# panocama.net
KiCad netlist of a schematic drawn in EAGLE
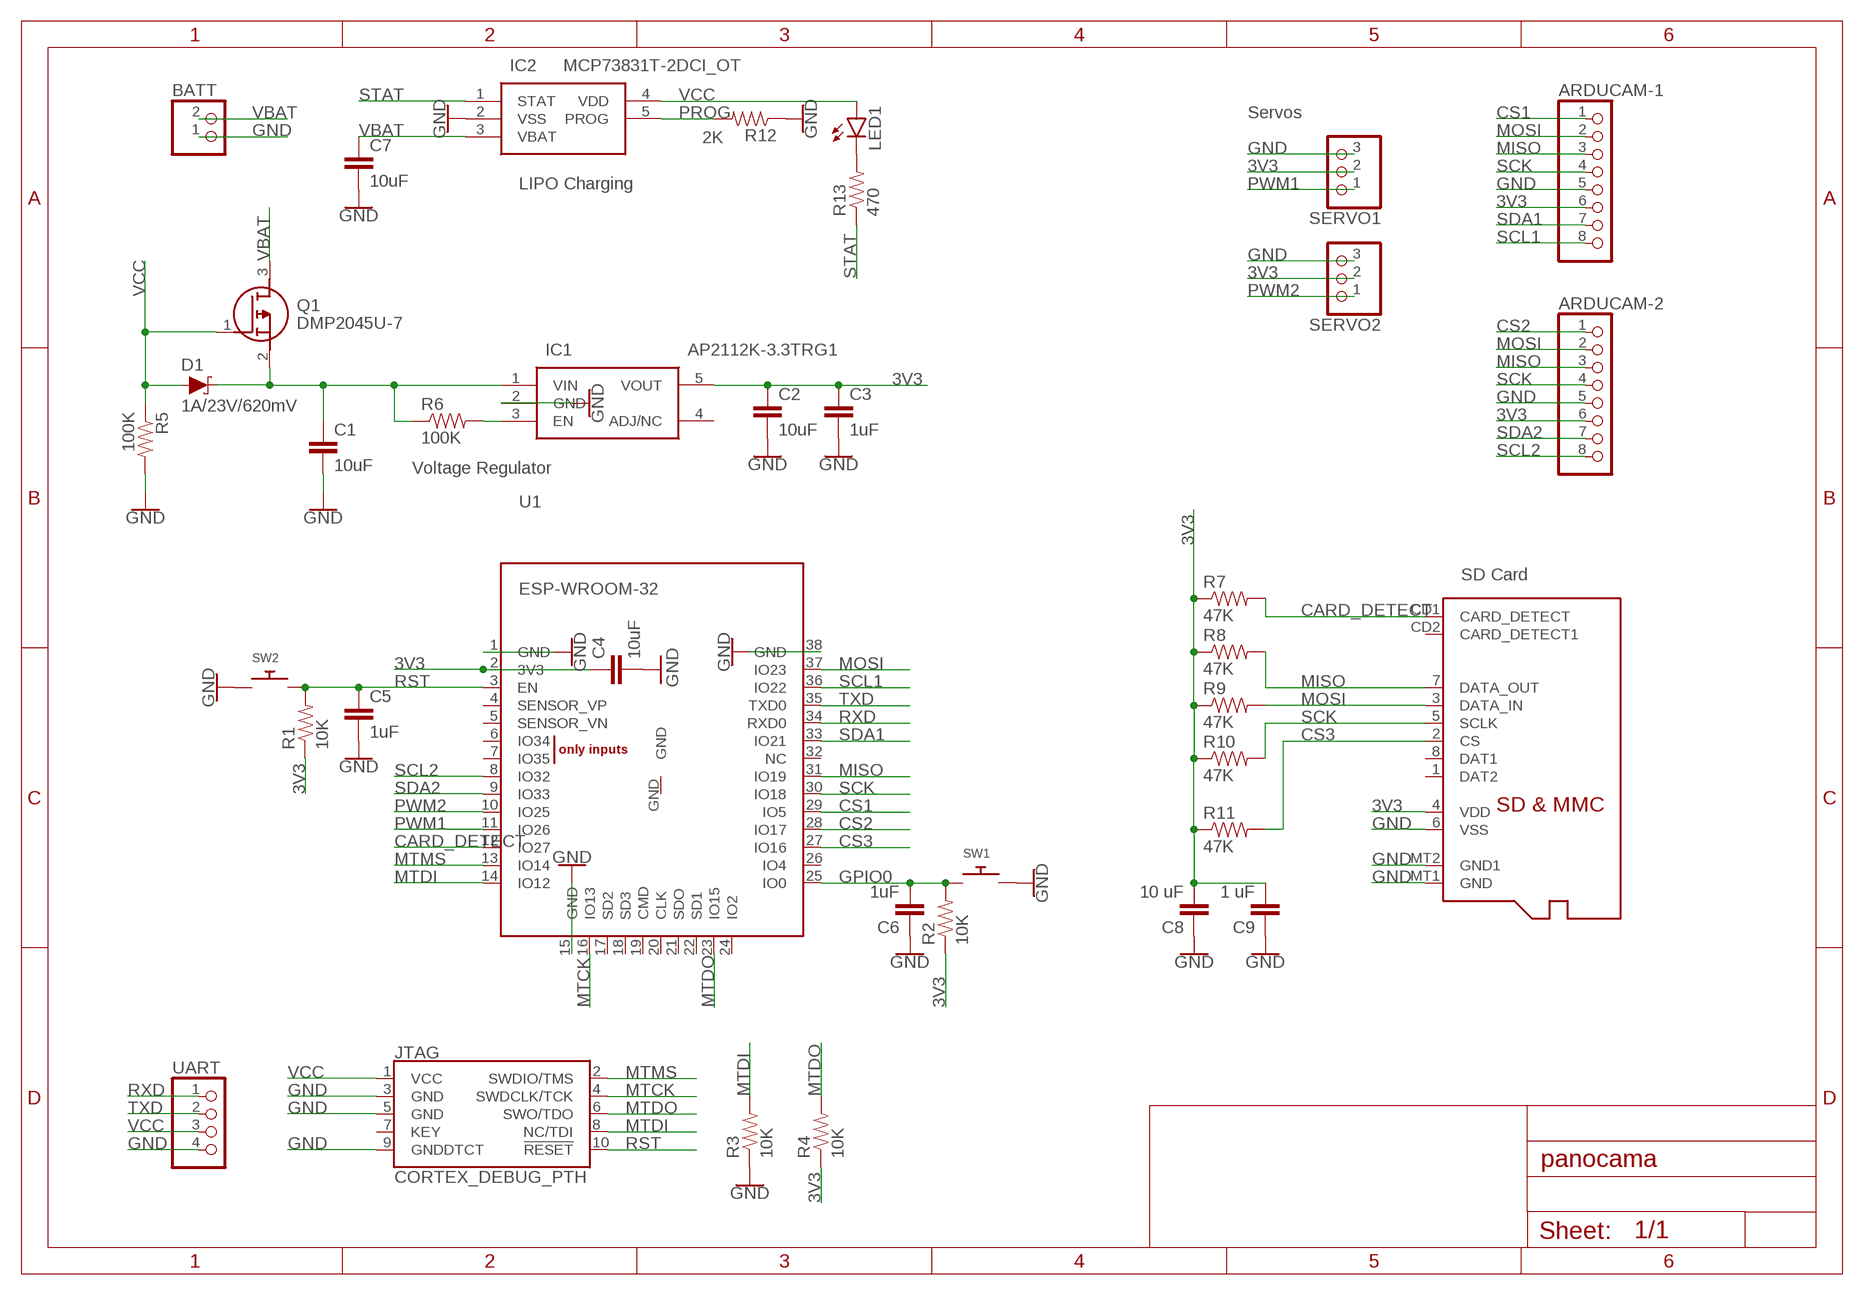
[diagram p0: schematic, sheet 1]

(export (version "E")
  (design (tool "Eeschema 10.0.6"))
  (components
    (comp (ref "ARDUCAM-1")
      (value "PINHD-1X8CLEANBIG")
      (footprint "eagle-import:1X08-CLEANBIG")
      (libsource (lib "eagle-import") (part "PINHD-1X8CLEANBIG"))
    )
    (comp (ref "ARDUCAM-2")
      (value "PINHD-1X8CLEANBIG")
      (footprint "eagle-import:1X08-CLEANBIG")
      (libsource (lib "eagle-import") (part "PINHD-1X8CLEANBIG"))
    )
    (comp (ref "BATT")
      (value "JST_2PIN-SMT")
      (footprint "eagle-import:JST-PH-2-SMT")
      (libsource (lib "eagle-import") (part "JST_2PIN-SMT"))
    )
    (comp (ref "C1")
      (value "10uF")
      (footprint "eagle-import:0805")
      (libsource (lib "eagle-import") (part "CAP"))
    )
    (comp (ref "C2")
      (value "10uF")
      (footprint "eagle-import:0805")
      (libsource (lib "eagle-import") (part "CAP"))
    )
    (comp (ref "C3")
      (value "1uF")
      (footprint "eagle-import:0805")
      (libsource (lib "eagle-import") (part "CAP"))
    )
    (comp (ref "C4")
      (value "10uF")
      (footprint "eagle-import:0805")
      (libsource (lib "eagle-import") (part "CAP"))
    )
    (comp (ref "C5")
      (value "1uF")
      (footprint "eagle-import:0805")
      (libsource (lib "eagle-import") (part "CAP"))
    )
    (comp (ref "C6")
      (value "1uF")
      (footprint "eagle-import:0805")
      (libsource (lib "eagle-import") (part "CAP"))
    )
    (comp (ref "C7")
      (value "10uF")
      (footprint "eagle-import:0805")
      (libsource (lib "eagle-import") (part "CAP"))
    )
    (comp (ref "C8")
      (value "10 uF")
      (footprint "eagle-import:0805")
      (libsource (lib "eagle-import") (part "CAP"))
    )
    (comp (ref "C9")
      (value "1 uF")
      (footprint "eagle-import:0805")
      (libsource (lib "eagle-import") (part "CAP"))
    )
    (comp (ref "D1")
      (value "1A/23V/620mV")
      (footprint "eagle-import:SOD-323")
      (libsource (lib "eagle-import") (part "DIODE-SCHOTTKY-BAT20J"))
    )
    (comp (ref "IC1")
      (value "AP2112K-3.3TRG1")
      (footprint "eagle-import:SOT95P282X130-5N")
      (fields (field (name "MOUSER_PART_NUMBER") "621-AP2112K-3.3TRG1"))
      (libsource (lib "eagle-import") (part "AP2112K-3.3TRG1"))
    )
    (comp (ref "IC2")
      (value "MCP73831T-2DCI_OT")
      (footprint "eagle-import:SOT95P270X145-5N")
      (fields
        (field (name "ARROW_PART_NUMBER") "MCP73831T-2DCI/OT")
        (field (name "MOUSER_PART_NUMBER") "579-MCP73831T-2DCIOT")
      )
      (libsource (lib "eagle-import") (part "MCP73831T-2DCI_OT"))
    )
    (comp (ref "JTAG")
      (value "CORTEX_DEBUG_PTH")
      (footprint "eagle-import:2X5-PTH-1.27MM")
      (libsource (lib "eagle-import") (part "CORTEX_DEBUG_PTH"))
    )
    (comp (ref "LED1")
      (value "LED0603")
      (footprint "eagle-import:LED-0603")
      (libsource (lib "eagle-import") (part "LED0603"))
    )
    (comp (ref "Q1")
      (value "DMP2045U-7")
      (footprint "eagle-import:SOT96P240X110-3N")
      (fields (field (name "MOUSER_PART_NUMBER") "621-DMP2045U-7"))
      (libsource (lib "eagle-import") (part "DMP2045U-7"))
    )
    (comp (ref "R1")
      (value "10K")
      (footprint "eagle-import:0805")
      (libsource (lib "eagle-import") (part "RES"))
    )
    (comp (ref "R2")
      (value "10K")
      (footprint "eagle-import:0805")
      (libsource (lib "eagle-import") (part "RES"))
    )
    (comp (ref "R3")
      (value "10K")
      (footprint "eagle-import:0805")
      (libsource (lib "eagle-import") (part "RES"))
    )
    (comp (ref "R4")
      (value "10K")
      (footprint "eagle-import:0805")
      (libsource (lib "eagle-import") (part "RES"))
    )
    (comp (ref "R5")
      (value "100K")
      (footprint "eagle-import:0805")
      (libsource (lib "eagle-import") (part "RES"))
    )
    (comp (ref "R6")
      (value "100K")
      (footprint "eagle-import:0805")
      (libsource (lib "eagle-import") (part "RES"))
    )
    (comp (ref "R7")
      (value "47K")
      (footprint "eagle-import:0805")
      (libsource (lib "eagle-import") (part "RES"))
    )
    (comp (ref "R8")
      (value "47K")
      (footprint "eagle-import:0805")
      (libsource (lib "eagle-import") (part "RES"))
    )
    (comp (ref "R9")
      (value "47K")
      (footprint "eagle-import:0805")
      (libsource (lib "eagle-import") (part "RES"))
    )
    (comp (ref "R10")
      (value "47K")
      (footprint "eagle-import:0805")
      (libsource (lib "eagle-import") (part "RES"))
    )
    (comp (ref "R11")
      (value "47K")
      (footprint "eagle-import:0805")
      (libsource (lib "eagle-import") (part "RES"))
    )
    (comp (ref "R12")
      (value "2K")
      (footprint "eagle-import:0805")
      (libsource (lib "eagle-import") (part "RES"))
    )
    (comp (ref "R13")
      (value "470")
      (footprint "eagle-import:0805")
      (libsource (lib "eagle-import") (part "RES"))
    )
    (comp (ref "SD")
      (value "MICROSD")
      (footprint "eagle-import:MICROSD")
      (libsource (lib "eagle-import") (part "MICROSD"))
    )
    (comp (ref "SERVO1")
      (value "PINHD-1X3")
      (footprint "eagle-import:1X03")
      (libsource (lib "eagle-import") (part "PINHD-1X3"))
    )
    (comp (ref "SERVO2")
      (value "PINHD-1X3")
      (footprint "eagle-import:1X03")
      (libsource (lib "eagle-import") (part "PINHD-1X3"))
    )
    (comp (ref "SW1")
      (value "SWITCH_PUSHBUTTONSOFTTOUCHSMD_SJ")
      (footprint "eagle-import:PUSHBUTTON_SMD_SJ")
      (libsource (lib "eagle-import") (part "SWITCH_PUSHBUTTONSOFTTOUCHSMD_SJ"))
    )
    (comp (ref "SW2")
      (value "SWITCH_PUSHBUTTONSOFTTOUCHSMD_SJ")
      (footprint "eagle-import:PUSHBUTTON_SMD_SJ")
      (libsource (lib "eagle-import") (part "SWITCH_PUSHBUTTONSOFTTOUCHSMD_SJ"))
    )
    (comp (ref "U1")
      (value "ESP-WROOM-32")
      (footprint "eagle-import:ESP-WROOM-32")
      (libsource (lib "eagle-import") (part "ESP-WROOM-32"))
    )
    (comp (ref "UART")
      (value "PINHD-1X4")
      (footprint "eagle-import:1X04")
      (libsource (lib "eagle-import") (part "PINHD-1X4"))
    )
  )
  (nets
    (net (code "1") (name "/3V3") (class "Default")
      (node (ref "ARDUCAM-1") (pin "6") (pinfunction "6_6") (pintype "passive"))
      (node (ref "ARDUCAM-2") (pin "6") (pinfunction "6_6") (pintype "passive"))
      (node (ref "C2") (pin "1") (pinfunction "1_1") (pintype "passive"))
      (node (ref "C3") (pin "1") (pinfunction "1_1") (pintype "passive"))
      (node (ref "C4") (pin "1") (pinfunction "1_1") (pintype "passive"))
      (node (ref "C8") (pin "2") (pinfunction "2_2") (pintype "passive"))
      (node (ref "C9") (pin "2") (pinfunction "2_2") (pintype "passive"))
      (node (ref "IC1") (pin "5") (pinfunction "VOUT_5") (pintype "bidirectional"))
      (node (ref "R1") (pin "1") (pinfunction "1_1") (pintype "passive"))
      (node (ref "R10") (pin "1") (pinfunction "1_1") (pintype "passive"))
      (node (ref "R11") (pin "1") (pinfunction "1_1") (pintype "passive"))
      (node (ref "R2") (pin "1") (pinfunction "1_1") (pintype "passive"))
      (node (ref "R4") (pin "1") (pinfunction "1_1") (pintype "passive"))
      (node (ref "R7") (pin "1") (pinfunction "1_1") (pintype "passive"))
      (node (ref "R8") (pin "1") (pinfunction "1_1") (pintype "passive"))
      (node (ref "R9") (pin "1") (pinfunction "1_1") (pintype "passive"))
      (node (ref "SD") (pin "4") (pinfunction "VDD_4") (pintype "power_in"))
      (node (ref "SERVO1") (pin "2") (pinfunction "2_2") (pintype "passive"))
      (node (ref "SERVO2") (pin "2") (pinfunction "2_2") (pintype "passive"))
      (node (ref "U1") (pin "2") (pinfunction "3V3_2") (pintype "bidirectional"))
    )
    (net (code "2") (name "/CARD_DETECT") (class "Default")
      (node (ref "R7") (pin "2") (pinfunction "2_2") (pintype "passive"))
      (node (ref "SD") (pin "CD1") (pinfunction "CARD_DETECT_CD1") (pintype "passive"))
      (node (ref "U1") (pin "12") (pinfunction "IO27_12") (pintype "bidirectional"))
    )
    (net (code "3") (name "/CS1") (class "Default")
      (node (ref "ARDUCAM-1") (pin "1") (pinfunction "1_1") (pintype "passive"))
      (node (ref "U1") (pin "29") (pinfunction "IO5_29") (pintype "bidirectional"))
    )
    (net (code "4") (name "/CS2") (class "Default")
      (node (ref "ARDUCAM-2") (pin "1") (pinfunction "1_1") (pintype "passive"))
      (node (ref "U1") (pin "28") (pinfunction "IO17_28") (pintype "bidirectional"))
    )
    (net (code "5") (name "/CS3") (class "Default")
      (node (ref "R11") (pin "2") (pinfunction "2_2") (pintype "passive"))
      (node (ref "SD") (pin "2") (pinfunction "CS_2") (pintype "input"))
      (node (ref "U1") (pin "27") (pinfunction "IO16_27") (pintype "bidirectional"))
    )
    (net (code "6") (name "/GPIO0") (class "Default")
      (node (ref "C6") (pin "2") (pinfunction "2_2") (pintype "passive"))
      (node (ref "R2") (pin "2") (pinfunction "2_2") (pintype "passive"))
      (node (ref "SW1") (pin "P$1") (pinfunction "P$1_P$1") (pintype "passive"))
      (node (ref "U1") (pin "25") (pinfunction "IO0_25") (pintype "bidirectional"))
    )
    (net (code "7") (name "/MISO") (class "Default")
      (node (ref "ARDUCAM-1") (pin "3") (pinfunction "3_3") (pintype "passive"))
      (node (ref "ARDUCAM-2") (pin "3") (pinfunction "3_3") (pintype "passive"))
      (node (ref "R8") (pin "2") (pinfunction "2_2") (pintype "passive"))
      (node (ref "SD") (pin "7") (pinfunction "DATA_OUT_7") (pintype "output"))
      (node (ref "U1") (pin "31") (pinfunction "IO19_31") (pintype "bidirectional"))
    )
    (net (code "8") (name "/MOSI") (class "Default")
      (node (ref "ARDUCAM-1") (pin "2") (pinfunction "2_2") (pintype "passive"))
      (node (ref "ARDUCAM-2") (pin "2") (pinfunction "2_2") (pintype "passive"))
      (node (ref "R9") (pin "2") (pinfunction "2_2") (pintype "passive"))
      (node (ref "SD") (pin "3") (pinfunction "DATA_IN_3") (pintype "input"))
      (node (ref "U1") (pin "37") (pinfunction "IO23_37") (pintype "bidirectional"))
    )
    (net (code "9") (name "/MTCK") (class "Default")
      (node (ref "JTAG") (pin "4") (pinfunction "SWDCLK/TCK_4") (pintype "bidirectional"))
      (node (ref "U1") (pin "16") (pinfunction "IO13_16") (pintype "bidirectional"))
    )
    (net (code "10") (name "/MTDI") (class "Default")
      (node (ref "JTAG") (pin "8") (pinfunction "NC/TDI_8") (pintype "bidirectional"))
      (node (ref "R3") (pin "2") (pinfunction "2_2") (pintype "passive"))
      (node (ref "U1") (pin "14") (pinfunction "IO12_14") (pintype "bidirectional"))
    )
    (net (code "11") (name "/MTDO") (class "Default")
      (node (ref "JTAG") (pin "6") (pinfunction "SWO/TDO_6") (pintype "bidirectional"))
      (node (ref "R4") (pin "2") (pinfunction "2_2") (pintype "passive"))
      (node (ref "U1") (pin "23") (pinfunction "IO15_23") (pintype "bidirectional"))
    )
    (net (code "12") (name "/MTMS") (class "Default")
      (node (ref "JTAG") (pin "2") (pinfunction "SWDIO/TMS_2") (pintype "bidirectional"))
      (node (ref "U1") (pin "13") (pinfunction "IO14_13") (pintype "bidirectional"))
    )
    (net (code "13") (name "/PROG") (class "Default")
      (node (ref "IC2") (pin "5") (pinfunction "PROG_5") (pintype "bidirectional"))
      (node (ref "R12") (pin "2") (pinfunction "2_2") (pintype "passive"))
    )
    (net (code "14") (name "/PWM1") (class "Default")
      (node (ref "SERVO1") (pin "1") (pinfunction "1_1") (pintype "passive"))
      (node (ref "U1") (pin "11") (pinfunction "IO26_11") (pintype "bidirectional"))
    )
    (net (code "15") (name "/PWM2") (class "Default")
      (node (ref "SERVO2") (pin "1") (pinfunction "1_1") (pintype "passive"))
      (node (ref "U1") (pin "10") (pinfunction "IO25_10") (pintype "bidirectional"))
    )
    (net (code "16") (name "/RST") (class "Default")
      (node (ref "C5") (pin "1") (pinfunction "1_1") (pintype "passive"))
      (node (ref "JTAG") (pin "10") (pinfunction "~{RESET}_10") (pintype "bidirectional"))
      (node (ref "R1") (pin "2") (pinfunction "2_2") (pintype "passive"))
      (node (ref "SW2") (pin "P$2") (pinfunction "P$2_P$2") (pintype "passive"))
      (node (ref "U1") (pin "3") (pinfunction "EN_3") (pintype "bidirectional"))
    )
    (net (code "17") (name "/RXD") (class "Default")
      (node (ref "U1") (pin "34") (pinfunction "RXD0_34") (pintype "bidirectional"))
      (node (ref "UART") (pin "1") (pinfunction "1_1") (pintype "passive"))
    )
    (net (code "18") (name "/SCK") (class "Default")
      (node (ref "ARDUCAM-1") (pin "4") (pinfunction "4_4") (pintype "passive"))
      (node (ref "ARDUCAM-2") (pin "4") (pinfunction "4_4") (pintype "passive"))
      (node (ref "R10") (pin "2") (pinfunction "2_2") (pintype "passive"))
      (node (ref "SD") (pin "5") (pinfunction "SCLK_5") (pintype "input"))
      (node (ref "U1") (pin "30") (pinfunction "IO18_30") (pintype "bidirectional"))
    )
    (net (code "19") (name "/SCL1") (class "Default")
      (node (ref "ARDUCAM-1") (pin "8") (pinfunction "8_8") (pintype "passive"))
      (node (ref "U1") (pin "36") (pinfunction "IO22_36") (pintype "bidirectional"))
    )
    (net (code "20") (name "/SCL2") (class "Default")
      (node (ref "ARDUCAM-2") (pin "8") (pinfunction "8_8") (pintype "passive"))
      (node (ref "U1") (pin "8") (pinfunction "IO32_8") (pintype "bidirectional"))
    )
    (net (code "21") (name "/SDA1") (class "Default")
      (node (ref "ARDUCAM-1") (pin "7") (pinfunction "7_7") (pintype "passive"))
      (node (ref "U1") (pin "33") (pinfunction "IO21_33") (pintype "bidirectional"))
    )
    (net (code "22") (name "/SDA2") (class "Default")
      (node (ref "ARDUCAM-2") (pin "7") (pinfunction "7_7") (pintype "passive"))
      (node (ref "U1") (pin "9") (pinfunction "IO33_9") (pintype "bidirectional"))
    )
    (net (code "23") (name "/STAT") (class "Default")
      (node (ref "IC2") (pin "1") (pinfunction "STAT_1") (pintype "bidirectional"))
      (node (ref "R13") (pin "1") (pinfunction "1_1") (pintype "passive"))
    )
    (net (code "24") (name "/TXD") (class "Default")
      (node (ref "U1") (pin "35") (pinfunction "TXD0_35") (pintype "bidirectional"))
      (node (ref "UART") (pin "2") (pinfunction "2_2") (pintype "passive"))
    )
    (net (code "25") (name "/VBAT") (class "Default")
      (node (ref "BATT") (pin "2") (pinfunction "1_2") (pintype "passive"))
      (node (ref "C7") (pin "1") (pinfunction "1_1") (pintype "passive"))
      (node (ref "IC2") (pin "3") (pinfunction "VBAT_3") (pintype "bidirectional"))
      (node (ref "Q1") (pin "3") (pinfunction "D_3") (pintype "bidirectional"))
    )
    (net (code "26") (name "/VCC") (class "Default")
      (node (ref "D1") (pin "A") (pinfunction "A_A") (pintype "passive"))
      (node (ref "IC2") (pin "4") (pinfunction "VDD_4") (pintype "bidirectional"))
      (node (ref "JTAG") (pin "1") (pinfunction "VCC_1") (pintype "bidirectional"))
      (node (ref "LED1") (pin "A") (pinfunction "A_A") (pintype "passive"))
      (node (ref "Q1") (pin "1") (pinfunction "G_1") (pintype "bidirectional"))
      (node (ref "R5") (pin "1") (pinfunction "1_1") (pintype "passive"))
      (node (ref "UART") (pin "3") (pinfunction "3_3") (pintype "passive"))
    )
    (net (code "27") (name "GND") (class "Default")
      (node (ref "ARDUCAM-1") (pin "5") (pinfunction "5_5") (pintype "passive"))
      (node (ref "ARDUCAM-2") (pin "5") (pinfunction "5_5") (pintype "passive"))
      (node (ref "BATT") (pin "1") (pinfunction "2_1") (pintype "passive"))
      (node (ref "C1") (pin "2") (pinfunction "2_2") (pintype "passive"))
      (node (ref "C2") (pin "2") (pinfunction "2_2") (pintype "passive"))
      (node (ref "C3") (pin "2") (pinfunction "2_2") (pintype "passive"))
      (node (ref "C4") (pin "2") (pinfunction "2_2") (pintype "passive"))
      (node (ref "C5") (pin "2") (pinfunction "2_2") (pintype "passive"))
      (node (ref "C6") (pin "1") (pinfunction "1_1") (pintype "passive"))
      (node (ref "C7") (pin "2") (pinfunction "2_2") (pintype "passive"))
      (node (ref "C8") (pin "1") (pinfunction "1_1") (pintype "passive"))
      (node (ref "C9") (pin "1") (pinfunction "1_1") (pintype "passive"))
      (node (ref "IC1") (pin "2") (pinfunction "GND_2") (pintype "bidirectional"))
      (node (ref "IC2") (pin "2") (pinfunction "VSS_2") (pintype "bidirectional"))
      (node (ref "JTAG") (pin "3") (pinfunction "GND_3") (pintype "bidirectional"))
      (node (ref "JTAG") (pin "5") (pinfunction "GND_5") (pintype "bidirectional"))
      (node (ref "JTAG") (pin "9") (pinfunction "GNDDTCT_9") (pintype "bidirectional"))
      (node (ref "R12") (pin "1") (pinfunction "1_1") (pintype "passive"))
      (node (ref "R3") (pin "1") (pinfunction "1_1") (pintype "passive"))
      (node (ref "R5") (pin "2") (pinfunction "2_2") (pintype "passive"))
      (node (ref "SD") (pin "6") (pinfunction "VSS_6") (pintype "power_in"))
      (node (ref "SD") (pin "MT1") (pinfunction "GND_MT1") (pintype "power_in"))
      (node (ref "SD") (pin "MT2") (pinfunction "GND1_MT2") (pintype "power_in"))
      (node (ref "SERVO1") (pin "3") (pinfunction "3_3") (pintype "passive"))
      (node (ref "SERVO2") (pin "3") (pinfunction "3_3") (pintype "passive"))
      (node (ref "SW1") (pin "P$2") (pinfunction "P$2_P$2") (pintype "passive"))
      (node (ref "SW2") (pin "P$1") (pinfunction "P$1_P$1") (pintype "passive"))
      (node (ref "U1") (pin "1") (pinfunction "GND_1") (pintype "bidirectional"))
      (node (ref "U1") (pin "15") (pinfunction "GND_15") (pintype "bidirectional"))
      (node (ref "U1") (pin "38") (pinfunction "GND_38") (pintype "bidirectional"))
      (node (ref "UART") (pin "4") (pinfunction "4_4") (pintype "passive"))
    )
    (net (code "28") (name "Net-(IC1-EN)") (class "Default")
      (node (ref "IC1") (pin "3") (pinfunction "EN_3") (pintype "bidirectional"))
      (node (ref "R6") (pin "2") (pinfunction "2_2") (pintype "passive"))
    )
    (net (code "29") (name "Net-(IC1-VIN)") (class "Default")
      (node (ref "C1") (pin "1") (pinfunction "1_1") (pintype "passive"))
      (node (ref "D1") (pin "C") (pinfunction "C_C") (pintype "passive"))
      (node (ref "IC1") (pin "1") (pinfunction "VIN_1") (pintype "bidirectional"))
      (node (ref "Q1") (pin "2") (pinfunction "S_2") (pintype "bidirectional"))
      (node (ref "R6") (pin "1") (pinfunction "1_1") (pintype "passive"))
    )
    (net (code "30") (name "Net-(LED1-PadC)") (class "Default")
      (node (ref "LED1") (pin "C") (pinfunction "C_C") (pintype "passive"))
      (node (ref "R13") (pin "2") (pinfunction "2_2") (pintype "passive"))
    )
    (net (code "31") (name "unconnected-(IC1-ADJ{slash}NC-Pad4)") (class "Default")
      (node (ref "IC1") (pin "4") (pinfunction "ADJ/NC_4") (pintype "bidirectional"))
    )
    (net (code "32") (name "unconnected-(JTAG-KEY-Pad7)") (class "Default")
      (node (ref "JTAG") (pin "7") (pinfunction "KEY_7") (pintype "bidirectional"))
    )
    (net (code "33") (name "unconnected-(SD-CARD_DETECT1-PadCD2)") (class "Default")
      (node (ref "SD") (pin "CD2") (pinfunction "CARD_DETECT1_CD2") (pintype "passive"))
    )
    (net (code "34") (name "unconnected-(SD-DAT1-Pad8)") (class "Default")
      (node (ref "SD") (pin "8") (pinfunction "DAT1_8") (pintype "bidirectional"))
    )
    (net (code "35") (name "unconnected-(SD-DAT2-Pad1)") (class "Default")
      (node (ref "SD") (pin "1") (pinfunction "DAT2_1") (pintype "bidirectional"))
    )
    (net (code "36") (name "unconnected-(U1-CLK-Pad20)") (class "Default")
      (node (ref "U1") (pin "20") (pinfunction "CLK_20") (pintype "bidirectional"))
    )
    (net (code "37") (name "unconnected-(U1-CMD-Pad19)") (class "Default")
      (node (ref "U1") (pin "19") (pinfunction "CMD_19") (pintype "bidirectional"))
    )
    (net (code "38") (name "unconnected-(U1-IO2-Pad24)") (class "Default")
      (node (ref "U1") (pin "24") (pinfunction "IO2_24") (pintype "bidirectional"))
    )
    (net (code "39") (name "unconnected-(U1-IO4-Pad26)") (class "Default")
      (node (ref "U1") (pin "26") (pinfunction "IO4_26") (pintype "bidirectional"))
    )
    (net (code "40") (name "unconnected-(U1-IO34-Pad6)") (class "Default")
      (node (ref "U1") (pin "6") (pinfunction "IO34_6") (pintype "input"))
    )
    (net (code "41") (name "unconnected-(U1-IO35-Pad7)") (class "Default")
      (node (ref "U1") (pin "7") (pinfunction "IO35_7") (pintype "input"))
    )
    (net (code "42") (name "unconnected-(U1-NC-Pad32)") (class "Default")
      (node (ref "U1") (pin "32") (pinfunction "NC_32") (pintype "bidirectional"))
    )
    (net (code "43") (name "unconnected-(U1-PadGND)") (class "Default")
      (node (ref "U1") (pin "GND") (pinfunction "GND_GND") (pintype "bidirectional"))
    )
    (net (code "44") (name "unconnected-(U1-SD1-Pad22)") (class "Default")
      (node (ref "U1") (pin "22") (pinfunction "SD1_22") (pintype "bidirectional"))
    )
    (net (code "45") (name "unconnected-(U1-SD2-Pad17)") (class "Default")
      (node (ref "U1") (pin "17") (pinfunction "SD2_17") (pintype "bidirectional"))
    )
    (net (code "46") (name "unconnected-(U1-SD3-Pad18)") (class "Default")
      (node (ref "U1") (pin "18") (pinfunction "SD3_18") (pintype "bidirectional"))
    )
    (net (code "47") (name "unconnected-(U1-SDO-Pad21)") (class "Default")
      (node (ref "U1") (pin "21") (pinfunction "SDO_21") (pintype "bidirectional"))
    )
    (net (code "48") (name "unconnected-(U1-SENSOR_VN-Pad5)") (class "Default")
      (node (ref "U1") (pin "5") (pinfunction "SENSOR_VN_5") (pintype "input"))
    )
    (net (code "49") (name "unconnected-(U1-SENSOR_VP-Pad4)") (class "Default")
      (node (ref "U1") (pin "4") (pinfunction "SENSOR_VP_4") (pintype "input"))
    )
  )
)
